# u_prog_with_esp12.net
KiCad netlist of a schematic drawn in EAGLE
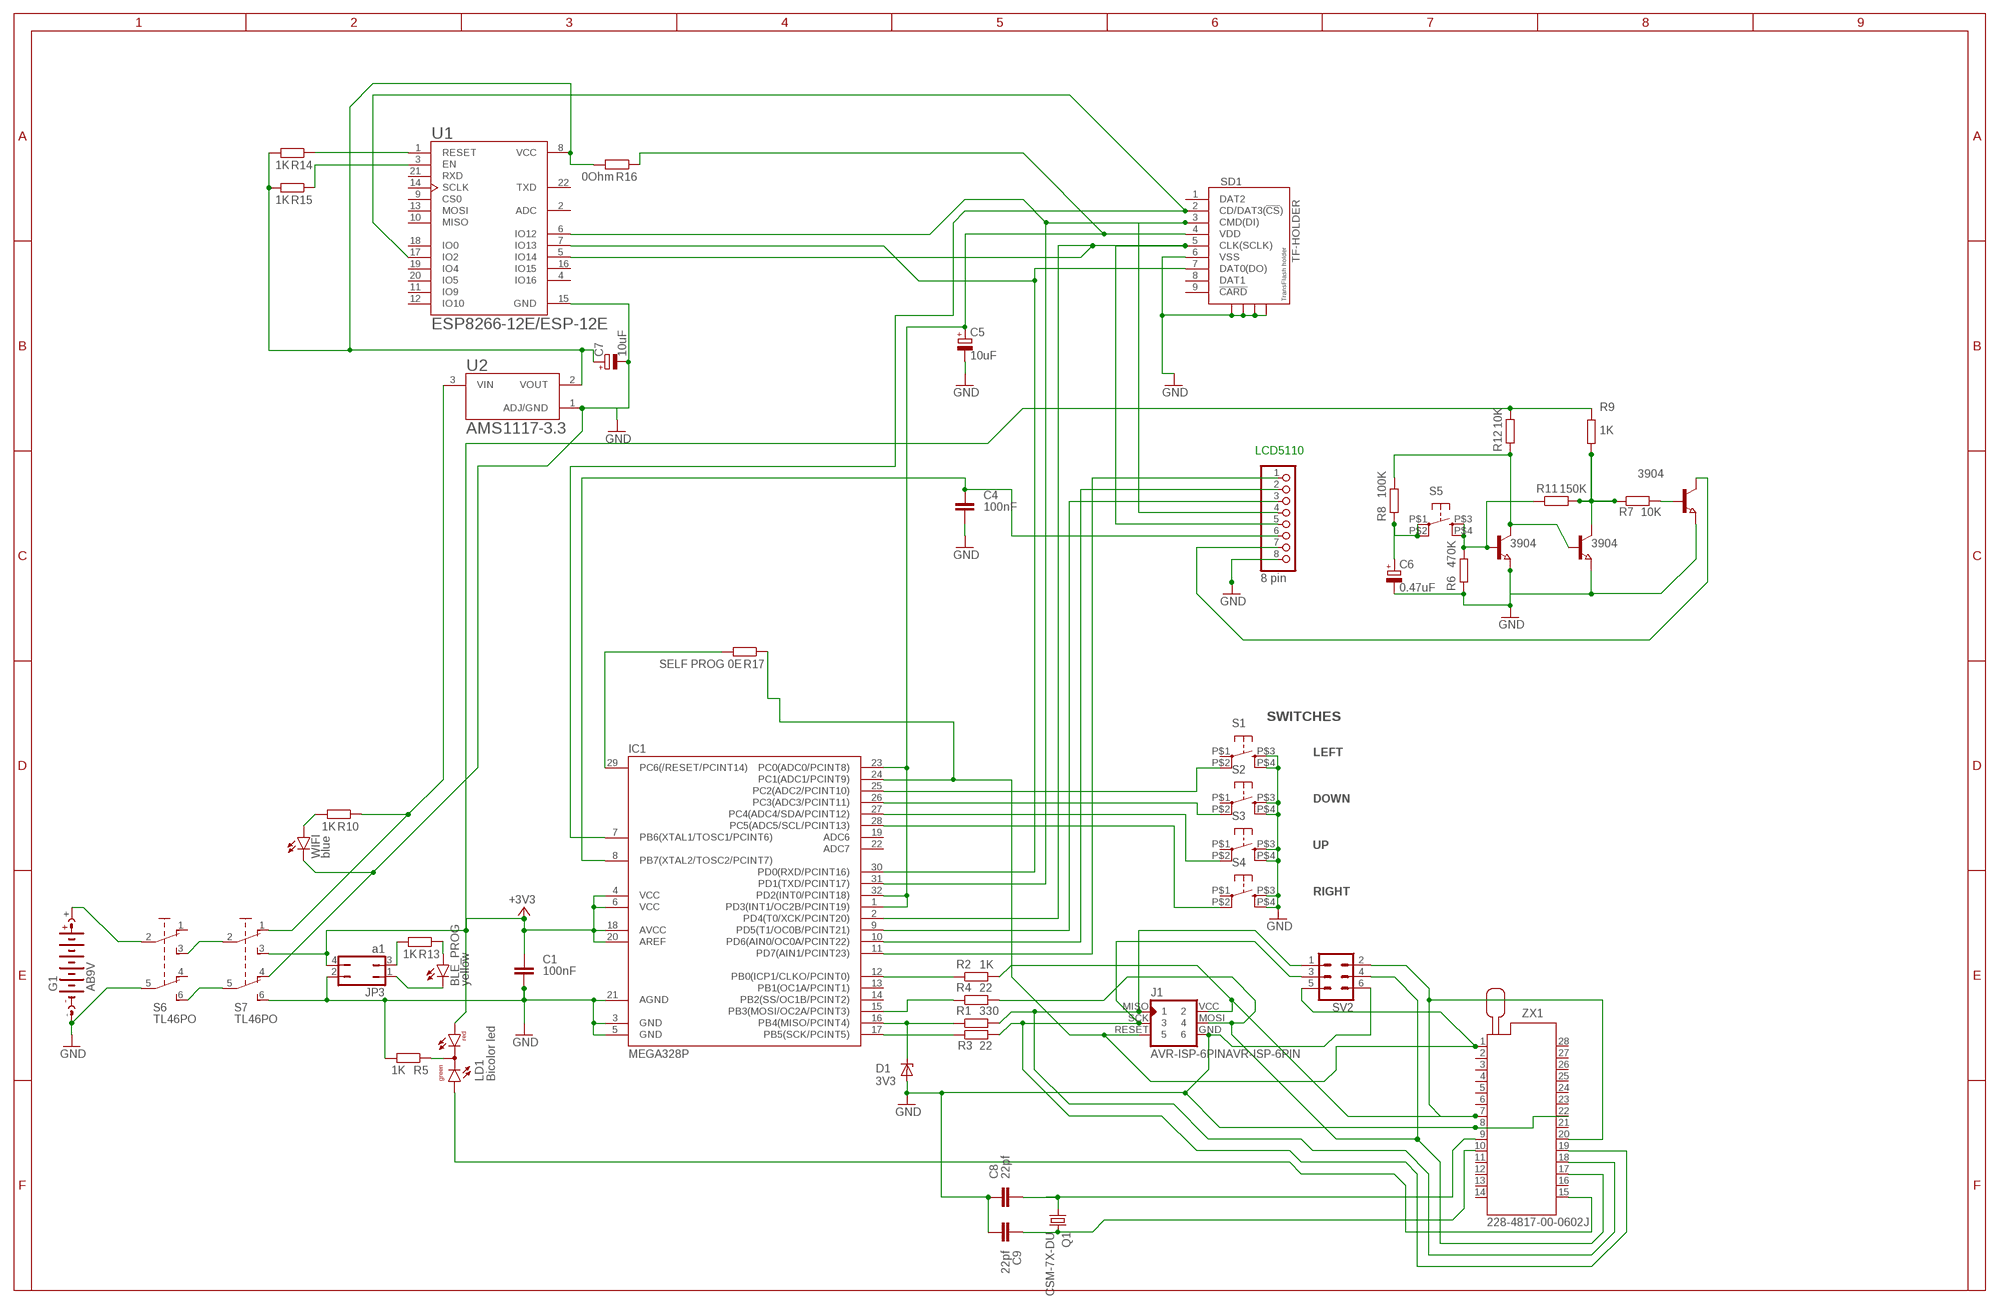
[diagram p0: schematic, sheet 1]

(export (version "E")
  (design (tool "Eeschema 10.0.6"))
  (components
    (comp (ref "BLE_PROG")
      (value "yellow")
      (footprint "eagle-import:LED5MM")
      (libsource (lib "eagle-import") (part "LED5MM"))
    )
    (comp (ref "C1")
      (value "100nF")
      (footprint "eagle-import:C0805")
      (libsource (lib "eagle-import") (part "C-EUC0805"))
    )
    (comp (ref "C4")
      (value "100nF")
      (footprint "eagle-import:C0805")
      (libsource (lib "eagle-import") (part "C-EUC0805"))
    )
    (comp (ref "C5")
      (value "10uF")
      (footprint "eagle-import:C_6032-28R")
      (libsource (lib "eagle-import") (part "CPOL-EUC/6032-28R"))
    )
    (comp (ref "C6")
      (value "0.47uF")
      (footprint "eagle-import:C_6032-28R")
      (libsource (lib "eagle-import") (part "CPOL-EUC/6032-28R"))
    )
    (comp (ref "C7")
      (value "10uF")
      (footprint "eagle-import:C_6032-28R")
      (libsource (lib "eagle-import") (part "CPOL-EUC/6032-28R"))
    )
    (comp (ref "C8")
      (value "22pf")
      (footprint "eagle-import:C0805")
      (libsource (lib "eagle-import") (part "C-EUC0805"))
    )
    (comp (ref "C9")
      (value "22pf")
      (footprint "eagle-import:C0805")
      (libsource (lib "eagle-import") (part "C-EUC0805"))
    )
    (comp (ref "D1")
      (value "3V3")
      (footprint "eagle-import:SOD80C")
      (libsource (lib "eagle-import") (part "ZENER-DIODESOD80C"))
    )
    (comp (ref "G1")
      (value "AB9V")
      (footprint "eagle-import:AB9V")
      (libsource (lib "eagle-import") (part "AB9V"))
    )
    (comp (ref "IC1")
      (value "MEGA328P")
      (footprint "eagle-import:TQFP32-08")
      (libsource (lib "eagle-import") (part "MEGA48/88/168-AU"))
    )
    (comp (ref "J1")
      (value "AVR-ISP-6PINAVR-ISP-6PIN")
      (footprint "eagle-import:AVR-ISP-6PIN")
      (libsource (lib "eagle-import") (part "AVR-ISP-6PINAVR-ISP-6PIN"))
    )
    (comp (ref "JP1")
      (value "8 pin")
      (footprint "eagle-import:1X08")
      (libsource (lib "eagle-import") (part "PINHD-1X8"))
    )
    (comp (ref "JP3")
      (value "a1")
      (footprint "eagle-import:JP2Q")
      (libsource (lib "eagle-import") (part "JP2Q"))
    )
    (comp (ref "LD1")
      (value "Bicolor led")
      (footprint "eagle-import:DUOLED-C-5MM")
      (libsource (lib "eagle-import") (part "DUOLED-RG-C"))
    )
    (comp (ref "Q1")
      (value "CSM-7X-DU")
      (footprint "eagle-import:CSM-7X-DU")
      (libsource (lib "eagle-import") (part "CSM-7X-DU"))
    )
    (comp (ref "Q2")
      (value "3904")
      (footprint "eagle-import:SOT23")
      (libsource (lib "eagle-import") (part "NPN-TRANSISTOR_SOT23"))
    )
    (comp (ref "Q3")
      (value "3904")
      (footprint "eagle-import:SOT23")
      (libsource (lib "eagle-import") (part "NPN-TRANSISTOR_SOT23"))
    )
    (comp (ref "Q4")
      (value "3904")
      (footprint "eagle-import:SOT23")
      (libsource (lib "eagle-import") (part "NPN-TRANSISTOR_SOT23"))
    )
    (comp (ref "R1")
      (value "330")
      (footprint "eagle-import:R0805")
      (libsource (lib "eagle-import") (part "R-EU_R0805"))
    )
    (comp (ref "R2")
      (value "1K")
      (footprint "eagle-import:R0805")
      (libsource (lib "eagle-import") (part "R-EU_R0805"))
    )
    (comp (ref "R3")
      (value "22")
      (footprint "eagle-import:R0805")
      (libsource (lib "eagle-import") (part "R-EU_R0805"))
    )
    (comp (ref "R4")
      (value "22")
      (footprint "eagle-import:R0805")
      (libsource (lib "eagle-import") (part "R-EU_R0805"))
    )
    (comp (ref "R5")
      (value "1K")
      (footprint "eagle-import:R0805")
      (libsource (lib "eagle-import") (part "R-EU_R0805"))
    )
    (comp (ref "R6")
      (value "470K")
      (footprint "eagle-import:R0805")
      (libsource (lib "eagle-import") (part "R-EU_R0805"))
    )
    (comp (ref "R7")
      (value "10K")
      (footprint "eagle-import:R0805")
      (libsource (lib "eagle-import") (part "R-EU_R0805"))
    )
    (comp (ref "R8")
      (value "100K")
      (footprint "eagle-import:R0805")
      (libsource (lib "eagle-import") (part "R-EU_R0805"))
    )
    (comp (ref "R9")
      (value "1K")
      (footprint "eagle-import:R0805")
      (libsource (lib "eagle-import") (part "R-EU_R0805"))
    )
    (comp (ref "R10")
      (value "1K")
      (footprint "eagle-import:R0805")
      (libsource (lib "eagle-import") (part "R-EU_R0805"))
    )
    (comp (ref "R11")
      (value "150K")
      (footprint "eagle-import:R0805")
      (libsource (lib "eagle-import") (part "R-EU_R0805"))
    )
    (comp (ref "R12")
      (value "10K")
      (footprint "eagle-import:R0805")
      (libsource (lib "eagle-import") (part "R-EU_R0805"))
    )
    (comp (ref "R13")
      (value "1K")
      (footprint "eagle-import:R0805")
      (libsource (lib "eagle-import") (part "R-EU_R0805"))
    )
    (comp (ref "R14")
      (value "1K")
      (footprint "eagle-import:R0805")
      (libsource (lib "eagle-import") (part "R-EU_R0805"))
    )
    (comp (ref "R15")
      (value "1K")
      (footprint "eagle-import:R0805")
      (libsource (lib "eagle-import") (part "R-EU_R0805"))
    )
    (comp (ref "R16")
      (value "0Ohm")
      (footprint "eagle-import:R0805")
      (libsource (lib "eagle-import") (part "R-EU_R0805"))
    )
    (comp (ref "R17")
      (value "SELF PROG 0E")
      (footprint "eagle-import:R0805")
      (libsource (lib "eagle-import") (part "R-EU_R0805"))
    )
    (comp (ref "S1")
      (value "10-XX-SMD")
      (footprint "eagle-import:B3F-10XX-SMD")
      (libsource (lib "eagle-import") (part "10-XX-SMD"))
    )
    (comp (ref "S2")
      (value "10-XX-SMD")
      (footprint "eagle-import:B3F-10XX-SMD")
      (libsource (lib "eagle-import") (part "10-XX-SMD"))
    )
    (comp (ref "S3")
      (value "10-XX-SMD")
      (footprint "eagle-import:B3F-10XX-SMD")
      (libsource (lib "eagle-import") (part "10-XX-SMD"))
    )
    (comp (ref "S4")
      (value "10-XX-SMD")
      (footprint "eagle-import:B3F-10XX-SMD")
      (libsource (lib "eagle-import") (part "10-XX-SMD"))
    )
    (comp (ref "S5")
      (value "10-XX-SMD")
      (footprint "eagle-import:B3F-10XX-SMD")
      (libsource (lib "eagle-import") (part "10-XX-SMD"))
    )
    (comp (ref "S6")
      (value "TL46PO")
      (footprint "eagle-import:TL4XPO")
      (libsource (lib "eagle-import") (part "TL46PO"))
    )
    (comp (ref "S7")
      (value "TL46PO")
      (footprint "eagle-import:TL4XPO")
      (libsource (lib "eagle-import") (part "TL46PO"))
    )
    (comp (ref "SD1")
      (value "TF-HOLDER")
      (footprint "eagle-import:TF-PULL")
      (libsource (lib "eagle-import") (part "TF-HOLDER"))
    )
    (comp (ref "SV2")
      (value "MA03-2")
      (footprint "eagle-import:MA03-2")
      (libsource (lib "eagle-import") (part "MA03-2"))
    )
    (comp (ref "U1")
      (value "ESP8266-12E/ESP-12E")
      (footprint "eagle-import:XCVR_ESP8266-12E_ESP-12E")
      (fields (field (name "MF") "AI-Thinker"))
      (libsource (lib "eagle-import") (part "ESP8266-12E/ESP-12E"))
    )
    (comp (ref "U2")
      (value "AMS1117-3.3")
      (footprint "eagle-import:SOT229P700X180-4N")
      (fields (field (name "MF") "Advanced Monolithic Systems"))
      (libsource (lib "eagle-import") (part "AMS1117-3.3"))
    )
    (comp (ref "WIFI")
      (value "blue")
      (footprint "eagle-import:LED5MM")
      (libsource (lib "eagle-import") (part "LED5MM"))
    )
    (comp (ref "ZX1")
      (value "228-4817-00-0602J")
      (footprint "eagle-import:228-4817-00-0602J")
      (fields (field (name "MF") "3M"))
      (libsource (lib "eagle-import") (part "228-?00-0602J4817-"))
    )
  )
  (nets
    (net (code "1") (name "+3V3") (class "Default")
      (node (ref "C1") (pin "1") (pinfunction "1_1") (pintype "passive"))
      (node (ref "IC1") (pin "18") (pinfunction "AVCC_18") (pintype "passive"))
      (node (ref "IC1") (pin "20") (pinfunction "AREF_20") (pintype "passive"))
      (node (ref "IC1") (pin "4") (pinfunction "VCC_4") (pintype "power_in"))
      (node (ref "IC1") (pin "6") (pinfunction "VCC_6") (pintype "power_in"))
      (node (ref "JP3") (pin "4") (pinfunction "4_4") (pintype "passive"))
      (node (ref "LD1") (pin "AR") (pinfunction "AR_AR") (pintype "passive"))
      (node (ref "R12") (pin "2") (pinfunction "2_2") (pintype "passive"))
      (node (ref "R9") (pin "1") (pinfunction "1_1") (pintype "passive"))
      (node (ref "S7") (pin "3") (pinfunction "S_3") (pintype "passive"))
    )
    (net (code "2") (name "GND") (class "Default")
      (node (ref "C1") (pin "2") (pinfunction "2_2") (pintype "passive"))
      (node (ref "C4") (pin "2") (pinfunction "2_2") (pintype "passive"))
      (node (ref "C5") (pin "-") (pinfunction "-_-") (pintype "passive"))
      (node (ref "C6") (pin "-") (pinfunction "-_-") (pintype "passive"))
      (node (ref "C7") (pin "-") (pinfunction "-_-") (pintype "passive"))
      (node (ref "C8") (pin "1") (pinfunction "1_1") (pintype "passive"))
      (node (ref "C9") (pin "2") (pinfunction "2_2") (pintype "passive"))
      (node (ref "D1") (pin "A") (pinfunction "A_A") (pintype "passive"))
      (node (ref "G1") (pin "-") (pinfunction "-_-") (pintype "passive"))
      (node (ref "IC1") (pin "21") (pinfunction "AGND_21") (pintype "power_in"))
      (node (ref "IC1") (pin "3") (pinfunction "GND_3") (pintype "power_in"))
      (node (ref "IC1") (pin "5") (pinfunction "GND_5") (pintype "power_in"))
      (node (ref "J1") (pin "GND") (pinfunction "6_GND") (pintype "passive"))
      (node (ref "JP1") (pin "8") (pinfunction "8_8") (pintype "passive"))
      (node (ref "JP3") (pin "2") (pinfunction "2_2") (pintype "passive"))
      (node (ref "Q2") (pin "2") (pinfunction "E_2") (pintype "passive"))
      (node (ref "Q3") (pin "2") (pinfunction "E_2") (pintype "passive"))
      (node (ref "Q4") (pin "2") (pinfunction "E_2") (pintype "passive"))
      (node (ref "R5") (pin "2") (pinfunction "2_2") (pintype "passive"))
      (node (ref "R6") (pin "1") (pinfunction "1_1") (pintype "passive"))
      (node (ref "S1") (pin "P$3") (pinfunction "S_P$3") (pintype "passive"))
      (node (ref "S1") (pin "P$4") (pinfunction "S1_P$4") (pintype "passive"))
      (node (ref "S2") (pin "P$3") (pinfunction "S_P$3") (pintype "passive"))
      (node (ref "S2") (pin "P$4") (pinfunction "S1_P$4") (pintype "passive"))
      (node (ref "S3") (pin "P$3") (pinfunction "S_P$3") (pintype "passive"))
      (node (ref "S3") (pin "P$4") (pinfunction "S1_P$4") (pintype "passive"))
      (node (ref "S4") (pin "P$3") (pinfunction "S_P$3") (pintype "passive"))
      (node (ref "S4") (pin "P$4") (pinfunction "S1_P$4") (pintype "passive"))
      (node (ref "S6") (pin "5") (pinfunction "P1_5") (pintype "passive"))
      (node (ref "S7") (pin "4") (pinfunction "O1_4") (pintype "passive"))
      (node (ref "S7") (pin "6") (pinfunction "S1_6") (pintype "passive"))
      (node (ref "SD1") (pin "6") (pinfunction "VSS_6") (pintype "power_in"))
      (node (ref "SD1") (pin "S1") (pinfunction "S1_S1") (pintype "passive"))
      (node (ref "SD1") (pin "S2") (pinfunction "S2_S2") (pintype "passive"))
      (node (ref "SD1") (pin "S3") (pinfunction "S3_S3") (pintype "passive"))
      (node (ref "SD1") (pin "S4") (pinfunction "S4_S4") (pintype "passive"))
      (node (ref "SV2") (pin "6") (pinfunction "6_6") (pintype "passive"))
      (node (ref "U1") (pin "15") (pinfunction "GND_15") (pintype "power_in"))
      (node (ref "U2") (pin "1") (pinfunction "ADJ/GND_1") (pintype "power_in"))
      (node (ref "WIFI") (pin "K") (pinfunction "C_K") (pintype "passive"))
      (node (ref "ZX1") (pin "22") (pinfunction "22_22") (pintype "passive"))
      (node (ref "ZX1") (pin "8") (pinfunction "8_8") (pintype "passive"))
    )
    (net (code "3") (name "Net-(BLE_PROG-C)") (class "Default")
      (node (ref "BLE_PROG") (pin "K") (pinfunction "C_K") (pintype "passive"))
      (node (ref "JP3") (pin "1") (pinfunction "1_1") (pintype "passive"))
    )
    (net (code "4") (name "Net-(BLE_PROG-PadA)") (class "Default")
      (node (ref "BLE_PROG") (pin "A") (pinfunction "A_A") (pintype "passive"))
      (node (ref "R13") (pin "1") (pinfunction "1_1") (pintype "passive"))
    )
    (net (code "5") (name "Net-(C8-Pad2)") (class "Default")
      (node (ref "C8") (pin "2") (pinfunction "2_2") (pintype "passive"))
      (node (ref "Q1") (pin "1") (pinfunction "1_1") (pintype "passive"))
      (node (ref "ZX1") (pin "9") (pinfunction "9_9") (pintype "passive"))
    )
    (net (code "6") (name "Net-(C9-Pad1)") (class "Default")
      (node (ref "C9") (pin "1") (pinfunction "1_1") (pintype "passive"))
      (node (ref "Q1") (pin "2") (pinfunction "2_2") (pintype "passive"))
      (node (ref "ZX1") (pin "10") (pinfunction "10_10") (pintype "passive"))
    )
    (net (code "7") (name "Net-(IC1-PB0(ICP1{slash}CLKO{slash}PCINT0))") (class "Default")
      (node (ref "IC1") (pin "12") (pinfunction "PB0(ICP1/CLKO/PCINT0)_12") (pintype "bidirectional"))
      (node (ref "R2") (pin "1") (pinfunction "1_1") (pintype "passive"))
    )
    (net (code "8") (name "Net-(IC1-PB3(MOSI{slash}OC2A{slash}PCINT3))") (class "Default")
      (node (ref "IC1") (pin "15") (pinfunction "PB3(MOSI/OC2A/PCINT3)_15") (pintype "bidirectional"))
      (node (ref "R4") (pin "1") (pinfunction "1_1") (pintype "passive"))
    )
    (net (code "9") (name "Net-(IC1-PB4(MISO{slash}PCINT4))") (class "Default")
      (node (ref "D1") (pin "C") (pinfunction "C_C") (pintype "passive"))
      (node (ref "IC1") (pin "16") (pinfunction "PB4(MISO/PCINT4)_16") (pintype "bidirectional"))
      (node (ref "R1") (pin "1") (pinfunction "1_1") (pintype "passive"))
    )
    (net (code "10") (name "Net-(IC1-PB5(SCK{slash}PCINT5))") (class "Default")
      (node (ref "IC1") (pin "17") (pinfunction "PB5(SCK/PCINT5)_17") (pintype "bidirectional"))
      (node (ref "R3") (pin "1") (pinfunction "1_1") (pintype "passive"))
    )
    (net (code "11") (name "Net-(IC1-PB6(XTAL1{slash}TOSC1{slash}PCINT6))") (class "Default")
      (node (ref "IC1") (pin "7") (pinfunction "PB6(XTAL1/TOSC1/PCINT6)_7") (pintype "bidirectional"))
      (node (ref "SD1") (pin "2") (pinfunction "CD/DAT3(~{CS})_2") (pintype "bidirectional"))
      (node (ref "U1") (pin "17") (pinfunction "IO2_17") (pintype "bidirectional"))
    )
    (net (code "12") (name "Net-(IC1-PB7(XTAL2{slash}TOSC2{slash}PCINT7))") (class "Default")
      (node (ref "C4") (pin "1") (pinfunction "1_1") (pintype "passive"))
      (node (ref "IC1") (pin "8") (pinfunction "PB7(XTAL2/TOSC2/PCINT7)_8") (pintype "bidirectional"))
      (node (ref "JP1") (pin "6") (pinfunction "6_6") (pintype "passive"))
    )
    (net (code "13") (name "Net-(IC1-PC0(ADC0{slash}PCINT8))") (class "Default")
      (node (ref "C5") (pin "+") (pinfunction "+_+") (pintype "passive"))
      (node (ref "IC1") (pin "1") (pinfunction "PD3(INT1/OC2B/PCINT19)_1") (pintype "bidirectional"))
      (node (ref "IC1") (pin "23") (pinfunction "PC0(ADC0/PCINT8)_23") (pintype "bidirectional"))
      (node (ref "IC1") (pin "32") (pinfunction "PD2(INT0/PCINT18)_32") (pintype "bidirectional"))
      (node (ref "R16") (pin "1") (pinfunction "1_1") (pintype "passive"))
      (node (ref "SD1") (pin "4") (pinfunction "VDD_4") (pintype "power_in"))
    )
    (net (code "14") (name "Net-(IC1-PC1(ADC1{slash}PCINT9))") (class "Default")
      (node (ref "IC1") (pin "24") (pinfunction "PC1(ADC1/PCINT9)_24") (pintype "bidirectional"))
      (node (ref "J1") (pin "RESET") (pinfunction "5_RESET") (pintype "passive"))
      (node (ref "R17") (pin "1") (pinfunction "1_1") (pintype "passive"))
      (node (ref "SV2") (pin "5") (pinfunction "5_5") (pintype "passive"))
      (node (ref "ZX1") (pin "1") (pinfunction "1_1") (pintype "passive"))
    )
    (net (code "15") (name "Net-(IC1-PC2(ADC2{slash}PCINT10))") (class "Default")
      (node (ref "IC1") (pin "25") (pinfunction "PC2(ADC2/PCINT10)_25") (pintype "bidirectional"))
      (node (ref "S1") (pin "P$2") (pinfunction "P1_P$2") (pintype "passive"))
    )
    (net (code "16") (name "Net-(IC1-PC3(ADC3{slash}PCINT11))") (class "Default")
      (node (ref "IC1") (pin "26") (pinfunction "PC3(ADC3/PCINT11)_26") (pintype "bidirectional"))
      (node (ref "S2") (pin "P$2") (pinfunction "P1_P$2") (pintype "passive"))
    )
    (net (code "17") (name "Net-(IC1-PC4(ADC4{slash}SDA{slash}PCINT12))") (class "Default")
      (node (ref "IC1") (pin "27") (pinfunction "PC4(ADC4/SDA/PCINT12)_27") (pintype "bidirectional"))
      (node (ref "S3") (pin "P$2") (pinfunction "P1_P$2") (pintype "passive"))
    )
    (net (code "18") (name "Net-(IC1-PC5(ADC5{slash}SCL{slash}PCINT13))") (class "Default")
      (node (ref "IC1") (pin "28") (pinfunction "PC5(ADC5/SCL/PCINT13)_28") (pintype "bidirectional"))
      (node (ref "S4") (pin "P$2") (pinfunction "P1_P$2") (pintype "passive"))
    )
    (net (code "19") (name "Net-(IC1-PC6({slash}RESET{slash}PCINT14))") (class "Default")
      (node (ref "IC1") (pin "29") (pinfunction "PC6(/RESET/PCINT14)_29") (pintype "bidirectional"))
      (node (ref "R17") (pin "2") (pinfunction "2_2") (pintype "passive"))
    )
    (net (code "20") (name "Net-(IC1-PD0(RXD{slash}PCINT16))") (class "Default")
      (node (ref "IC1") (pin "30") (pinfunction "PD0(RXD/PCINT16)_30") (pintype "bidirectional"))
      (node (ref "SD1") (pin "7") (pinfunction "DAT0(DO)_7") (pintype "bidirectional"))
      (node (ref "U1") (pin "7") (pinfunction "IO13_7") (pintype "bidirectional"))
    )
    (net (code "21") (name "Net-(IC1-PD1(TXD{slash}PCINT17))") (class "Default")
      (node (ref "IC1") (pin "31") (pinfunction "PD1(TXD/PCINT17)_31") (pintype "bidirectional"))
      (node (ref "JP1") (pin "4") (pinfunction "4_4") (pintype "passive"))
      (node (ref "SD1") (pin "3") (pinfunction "CMD(DI)_3") (pintype "bidirectional"))
      (node (ref "U1") (pin "6") (pinfunction "IO12_6") (pintype "bidirectional"))
    )
    (net (code "22") (name "Net-(IC1-PD4(T0{slash}XCK{slash}PCINT20))") (class "Default")
      (node (ref "IC1") (pin "2") (pinfunction "PD4(T0/XCK/PCINT20)_2") (pintype "bidirectional"))
      (node (ref "JP1") (pin "5") (pinfunction "5_5") (pintype "passive"))
      (node (ref "SD1") (pin "5") (pinfunction "CLK(SCLK)_5") (pintype "input"))
      (node (ref "U1") (pin "5") (pinfunction "IO14_5") (pintype "bidirectional"))
    )
    (net (code "23") (name "Net-(IC1-PD5(T1{slash}OC0B{slash}PCINT21))") (class "Default")
      (node (ref "IC1") (pin "9") (pinfunction "PD5(T1/OC0B/PCINT21)_9") (pintype "bidirectional"))
      (node (ref "JP1") (pin "3") (pinfunction "3_3") (pintype "passive"))
    )
    (net (code "24") (name "Net-(IC1-PD6(AIN0{slash}OC0A{slash}PCINT22))") (class "Default")
      (node (ref "IC1") (pin "10") (pinfunction "PD6(AIN0/OC0A/PCINT22)_10") (pintype "bidirectional"))
      (node (ref "JP1") (pin "2") (pinfunction "2_2") (pintype "passive"))
    )
    (net (code "25") (name "Net-(IC1-PD7(AIN1{slash}PCINT23))") (class "Default")
      (node (ref "IC1") (pin "11") (pinfunction "PD7(AIN1/PCINT23)_11") (pintype "bidirectional"))
      (node (ref "JP1") (pin "1") (pinfunction "1_1") (pintype "passive"))
    )
    (net (code "26") (name "Net-(J1-1)") (class "Default")
      (node (ref "J1") (pin "MISO") (pinfunction "1_MISO") (pintype "passive"))
      (node (ref "R1") (pin "2") (pinfunction "2_2") (pintype "passive"))
      (node (ref "SV2") (pin "1") (pinfunction "1_1") (pintype "passive"))
      (node (ref "ZX1") (pin "18") (pinfunction "18_18") (pintype "passive"))
    )
    (net (code "27") (name "Net-(J1-2)") (class "Default")
      (node (ref "J1") (pin "VCC") (pinfunction "2_VCC") (pintype "passive"))
      (node (ref "R2") (pin "2") (pinfunction "2_2") (pintype "passive"))
      (node (ref "SV2") (pin "2") (pinfunction "2_2") (pintype "passive"))
      (node (ref "ZX1") (pin "20") (pinfunction "20_20") (pintype "passive"))
      (node (ref "ZX1") (pin "7") (pinfunction "7_7") (pintype "passive"))
    )
    (net (code "28") (name "Net-(J1-3)") (class "Default")
      (node (ref "J1") (pin "SCK") (pinfunction "3_SCK") (pintype "passive"))
      (node (ref "R3") (pin "2") (pinfunction "2_2") (pintype "passive"))
      (node (ref "SV2") (pin "3") (pinfunction "3_3") (pintype "passive"))
      (node (ref "ZX1") (pin "19") (pinfunction "19_19") (pintype "passive"))
    )
    (net (code "29") (name "Net-(J1-4)") (class "Default")
      (node (ref "J1") (pin "MOSI") (pinfunction "4_MOSI") (pintype "passive"))
      (node (ref "R4") (pin "2") (pinfunction "2_2") (pintype "passive"))
      (node (ref "SV2") (pin "4") (pinfunction "4_4") (pintype "passive"))
      (node (ref "ZX1") (pin "17") (pinfunction "17_17") (pintype "passive"))
    )
    (net (code "30") (name "Net-(JP3-Pad3)") (class "Default")
      (node (ref "JP3") (pin "3") (pinfunction "3_3") (pintype "passive"))
      (node (ref "R13") (pin "2") (pinfunction "2_2") (pintype "passive"))
    )
    (net (code "31") (name "Net-(LD1-AG)") (class "Default")
      (node (ref "LD1") (pin "AX") (pinfunction "AG_AX") (pintype "passive"))
      (node (ref "ZX1") (pin "15") (pinfunction "15_15") (pintype "passive"))
    )
    (net (code "32") (name "Net-(LD1-PadC)") (class "Default")
      (node (ref "LD1") (pin "C") (pinfunction "C_C") (pintype "passive"))
      (node (ref "R5") (pin "1") (pinfunction "1_1") (pintype "passive"))
    )
    (net (code "33") (name "Net-(Q2-B)") (class "Default")
      (node (ref "Q2") (pin "1") (pinfunction "B_1") (pintype "passive"))
      (node (ref "R11") (pin "1") (pinfunction "1_1") (pintype "passive"))
      (node (ref "R6") (pin "2") (pinfunction "2_2") (pintype "passive"))
      (node (ref "S5") (pin "P$3") (pinfunction "S_P$3") (pintype "passive"))
      (node (ref "S5") (pin "P$4") (pinfunction "S1_P$4") (pintype "passive"))
    )
    (net (code "34") (name "Net-(Q2-C)") (class "Default")
      (node (ref "Q2") (pin "3") (pinfunction "C_3") (pintype "passive"))
      (node (ref "Q3") (pin "1") (pinfunction "B_1") (pintype "passive"))
      (node (ref "R12") (pin "1") (pinfunction "1_1") (pintype "passive"))
      (node (ref "R8") (pin "2") (pinfunction "2_2") (pintype "passive"))
    )
    (net (code "35") (name "Net-(Q3-C)") (class "Default")
      (node (ref "Q3") (pin "3") (pinfunction "C_3") (pintype "passive"))
      (node (ref "R11") (pin "2") (pinfunction "2_2") (pintype "passive"))
      (node (ref "R7") (pin "1") (pinfunction "1_1") (pintype "passive"))
      (node (ref "R9") (pin "2") (pinfunction "2_2") (pintype "passive"))
    )
    (net (code "36") (name "Net-(Q4-B)") (class "Default")
      (node (ref "Q4") (pin "1") (pinfunction "B_1") (pintype "passive"))
      (node (ref "R7") (pin "2") (pinfunction "2_2") (pintype "passive"))
    )
    (net (code "37") (name "Net-(Q4-C)") (class "Default")
      (node (ref "JP1") (pin "7") (pinfunction "7_7") (pintype "passive"))
      (node (ref "Q4") (pin "3") (pinfunction "C_3") (pintype "passive"))
    )
    (net (code "38") (name "Net-(R10-Pad2)") (class "Default")
      (node (ref "R10") (pin "2") (pinfunction "2_2") (pintype "passive"))
      (node (ref "WIFI") (pin "A") (pinfunction "A_A") (pintype "passive"))
    )
    (net (code "39") (name "Net-(S5-P)") (class "Default")
      (node (ref "C6") (pin "+") (pinfunction "+_+") (pintype "passive"))
      (node (ref "R8") (pin "1") (pinfunction "1_1") (pintype "passive"))
      (node (ref "S5") (pin "P$1") (pinfunction "P_P$1") (pintype "passive"))
      (node (ref "S5") (pin "P$2") (pinfunction "P1_P$2") (pintype "passive"))
    )
    (net (code "40") (name "Net-(S6-P)") (class "Default")
      (node (ref "G1") (pin "+") (pinfunction "+_+") (pintype "passive"))
      (node (ref "S6") (pin "2") (pinfunction "P_2") (pintype "passive"))
    )
    (net (code "41") (name "Net-(S6-S)") (class "Default")
      (node (ref "S6") (pin "3") (pinfunction "S_3") (pintype "passive"))
      (node (ref "S7") (pin "2") (pinfunction "P_2") (pintype "passive"))
    )
    (net (code "42") (name "Net-(S6-S1)") (class "Default")
      (node (ref "S6") (pin "6") (pinfunction "S1_6") (pintype "passive"))
      (node (ref "S7") (pin "5") (pinfunction "P1_5") (pintype "passive"))
    )
    (net (code "43") (name "Net-(S7-O)") (class "Default")
      (node (ref "R10") (pin "1") (pinfunction "1_1") (pintype "passive"))
      (node (ref "S7") (pin "1") (pinfunction "O_1") (pintype "passive"))
      (node (ref "U2") (pin "3") (pinfunction "VIN_3") (pintype "input"))
    )
    (net (code "44") (name "Net-(U1-EN)") (class "Default")
      (node (ref "R15") (pin "1") (pinfunction "1_1") (pintype "passive"))
      (node (ref "U1") (pin "3") (pinfunction "EN_3") (pintype "input"))
    )
    (net (code "45") (name "Net-(U1-RESET)") (class "Default")
      (node (ref "R14") (pin "1") (pinfunction "1_1") (pintype "passive"))
      (node (ref "U1") (pin "1") (pinfunction "RESET_1") (pintype "input"))
    )
    (net (code "46") (name "Net-(U1-VCC)") (class "Default")
      (node (ref "C7") (pin "+") (pinfunction "+_+") (pintype "passive"))
      (node (ref "R14") (pin "2") (pinfunction "2_2") (pintype "passive"))
      (node (ref "R15") (pin "2") (pinfunction "2_2") (pintype "passive"))
      (node (ref "R16") (pin "2") (pinfunction "2_2") (pintype "passive"))
      (node (ref "U1") (pin "8") (pinfunction "VCC_8") (pintype "power_in"))
      (node (ref "U2") (pin "2") (pinfunction "VOUT_2") (pintype "output"))
    )
    (net (code "47") (name "unconnected-(IC1-ADC6-Pad19)") (class "Default")
      (node (ref "IC1") (pin "19") (pinfunction "ADC6_19") (pintype "passive"))
    )
    (net (code "48") (name "unconnected-(IC1-ADC7-Pad22)") (class "Default")
      (node (ref "IC1") (pin "22") (pinfunction "ADC7_22") (pintype "passive"))
    )
    (net (code "49") (name "unconnected-(IC1-PB1(OC1A{slash}PCINT1)-Pad13)") (class "Default")
      (node (ref "IC1") (pin "13") (pinfunction "PB1(OC1A/PCINT1)_13") (pintype "bidirectional"))
    )
    (net (code "50") (name "unconnected-(IC1-PB2(SS{slash}OC1B{slash}PCINT2)-Pad14)") (class "Default")
      (node (ref "IC1") (pin "14") (pinfunction "PB2(SS/OC1B/PCINT2)_14") (pintype "bidirectional"))
    )
    (net (code "51") (name "unconnected-(S1-P-PadP$1)") (class "Default")
      (node (ref "S1") (pin "P$1") (pinfunction "P_P$1") (pintype "passive"))
    )
    (net (code "52") (name "unconnected-(S2-P-PadP$1)") (class "Default")
      (node (ref "S2") (pin "P$1") (pinfunction "P_P$1") (pintype "passive"))
    )
    (net (code "53") (name "unconnected-(S3-P-PadP$1)") (class "Default")
      (node (ref "S3") (pin "P$1") (pinfunction "P_P$1") (pintype "passive"))
    )
    (net (code "54") (name "unconnected-(S4-P-PadP$1)") (class "Default")
      (node (ref "S4") (pin "P$1") (pinfunction "P_P$1") (pintype "passive"))
    )
    (net (code "55") (name "unconnected-(S6-O-Pad1)") (class "Default")
      (node (ref "S6") (pin "1") (pinfunction "O_1") (pintype "passive"))
    )
    (net (code "56") (name "unconnected-(S6-O1-Pad4)") (class "Default")
      (node (ref "S6") (pin "4") (pinfunction "O1_4") (pintype "passive"))
    )
    (net (code "57") (name "unconnected-(SD1-DAT1-Pad8)") (class "Default")
      (node (ref "SD1") (pin "8") (pinfunction "DAT1_8") (pintype "bidirectional"))
    )
    (net (code "58") (name "unconnected-(SD1-DAT2-Pad1)") (class "Default")
      (node (ref "SD1") (pin "1") (pinfunction "DAT2_1") (pintype "bidirectional"))
    )
    (net (code "59") (name "unconnected-(SD1-~{CARD}-Pad9)") (class "Default")
      (node (ref "SD1") (pin "9") (pinfunction "~{CARD}_9") (pintype "passive"))
    )
    (net (code "60") (name "unconnected-(U1-ADC-Pad2)") (class "Default")
      (node (ref "U1") (pin "2") (pinfunction "ADC_2") (pintype "passive"))
    )
    (net (code "61") (name "unconnected-(U1-CS0-Pad9)") (class "Default")
      (node (ref "U1") (pin "9") (pinfunction "CS0_9") (pintype "input"))
    )
    (net (code "62") (name "unconnected-(U1-IO0-Pad18)") (class "Default")
      (node (ref "U1") (pin "18") (pinfunction "IO0_18") (pintype "bidirectional"))
    )
    (net (code "63") (name "unconnected-(U1-IO4-Pad19)") (class "Default")
      (node (ref "U1") (pin "19") (pinfunction "IO4_19") (pintype "bidirectional"))
    )
    (net (code "64") (name "unconnected-(U1-IO5-Pad20)") (class "Default")
      (node (ref "U1") (pin "20") (pinfunction "IO5_20") (pintype "bidirectional"))
    )
    (net (code "65") (name "unconnected-(U1-IO9-Pad11)") (class "Default")
      (node (ref "U1") (pin "11") (pinfunction "IO9_11") (pintype "bidirectional"))
    )
    (net (code "66") (name "unconnected-(U1-IO10-Pad12)") (class "Default")
      (node (ref "U1") (pin "12") (pinfunction "IO10_12") (pintype "bidirectional"))
    )
    (net (code "67") (name "unconnected-(U1-IO15-Pad16)") (class "Default")
      (node (ref "U1") (pin "16") (pinfunction "IO15_16") (pintype "bidirectional"))
    )
    (net (code "68") (name "unconnected-(U1-IO16-Pad4)") (class "Default")
      (node (ref "U1") (pin "4") (pinfunction "IO16_4") (pintype "bidirectional"))
    )
    (net (code "69") (name "unconnected-(U1-MISO-Pad10)") (class "Default")
      (node (ref "U1") (pin "10") (pinfunction "MISO_10") (pintype "bidirectional"))
    )
    (net (code "70") (name "unconnected-(U1-MOSI-Pad13)") (class "Default")
      (node (ref "U1") (pin "13") (pinfunction "MOSI_13") (pintype "bidirectional"))
    )
    (net (code "71") (name "unconnected-(U1-RXD-Pad21)") (class "Default")
      (node (ref "U1") (pin "21") (pinfunction "RXD_21") (pintype "input"))
    )
    (net (code "72") (name "unconnected-(U1-SCLK-Pad14)") (class "Default")
      (node (ref "U1") (pin "14") (pinfunction "SCLK_14") (pintype "input"))
    )
    (net (code "73") (name "unconnected-(U1-TXD-Pad22)") (class "Default")
      (node (ref "U1") (pin "22") (pinfunction "TXD_22") (pintype "output"))
    )
    (net (code "74") (name "unconnected-(ZX1-Pad2)") (class "Default")
      (node (ref "ZX1") (pin "2") (pinfunction "2_2") (pintype "passive"))
    )
    (net (code "75") (name "unconnected-(ZX1-Pad3)") (class "Default")
      (node (ref "ZX1") (pin "3") (pinfunction "3_3") (pintype "passive"))
    )
    (net (code "76") (name "unconnected-(ZX1-Pad4)") (class "Default")
      (node (ref "ZX1") (pin "4") (pinfunction "4_4") (pintype "passive"))
    )
    (net (code "77") (name "unconnected-(ZX1-Pad5)") (class "Default")
      (node (ref "ZX1") (pin "5") (pinfunction "5_5") (pintype "passive"))
    )
    (net (code "78") (name "unconnected-(ZX1-Pad6)") (class "Default")
      (node (ref "ZX1") (pin "6") (pinfunction "6_6") (pintype "passive"))
    )
    (net (code "79") (name "unconnected-(ZX1-Pad11)") (class "Default")
      (node (ref "ZX1") (pin "11") (pinfunction "11_11") (pintype "passive"))
    )
    (net (code "80") (name "unconnected-(ZX1-Pad12)") (class "Default")
      (node (ref "ZX1") (pin "12") (pinfunction "12_12") (pintype "passive"))
    )
    (net (code "81") (name "unconnected-(ZX1-Pad13)") (class "Default")
      (node (ref "ZX1") (pin "13") (pinfunction "13_13") (pintype "passive"))
    )
    (net (code "82") (name "unconnected-(ZX1-Pad14)") (class "Default")
      (node (ref "ZX1") (pin "14") (pinfunction "14_14") (pintype "passive"))
    )
    (net (code "83") (name "unconnected-(ZX1-Pad16)") (class "Default")
      (node (ref "ZX1") (pin "16") (pinfunction "16_16") (pintype "passive"))
    )
    (net (code "84") (name "unconnected-(ZX1-Pad21)") (class "Default")
      (node (ref "ZX1") (pin "21") (pinfunction "21_21") (pintype "passive"))
    )
    (net (code "85") (name "unconnected-(ZX1-Pad23)") (class "Default")
      (node (ref "ZX1") (pin "23") (pinfunction "23_23") (pintype "passive"))
    )
    (net (code "86") (name "unconnected-(ZX1-Pad24)") (class "Default")
      (node (ref "ZX1") (pin "24") (pinfunction "24_24") (pintype "passive"))
    )
    (net (code "87") (name "unconnected-(ZX1-Pad25)") (class "Default")
      (node (ref "ZX1") (pin "25") (pinfunction "25_25") (pintype "passive"))
    )
    (net (code "88") (name "unconnected-(ZX1-Pad26)") (class "Default")
      (node (ref "ZX1") (pin "26") (pinfunction "26_26") (pintype "passive"))
    )
    (net (code "89") (name "unconnected-(ZX1-Pad27)") (class "Default")
      (node (ref "ZX1") (pin "27") (pinfunction "27_27") (pintype "passive"))
    )
    (net (code "90") (name "unconnected-(ZX1-Pad28)") (class "Default")
      (node (ref "ZX1") (pin "28") (pinfunction "28_28") (pintype "passive"))
    )
  )
)
